# flipperzero-devboard-stlinkv3.net
KiCad netlist of a schematic drawn in Altium Designer
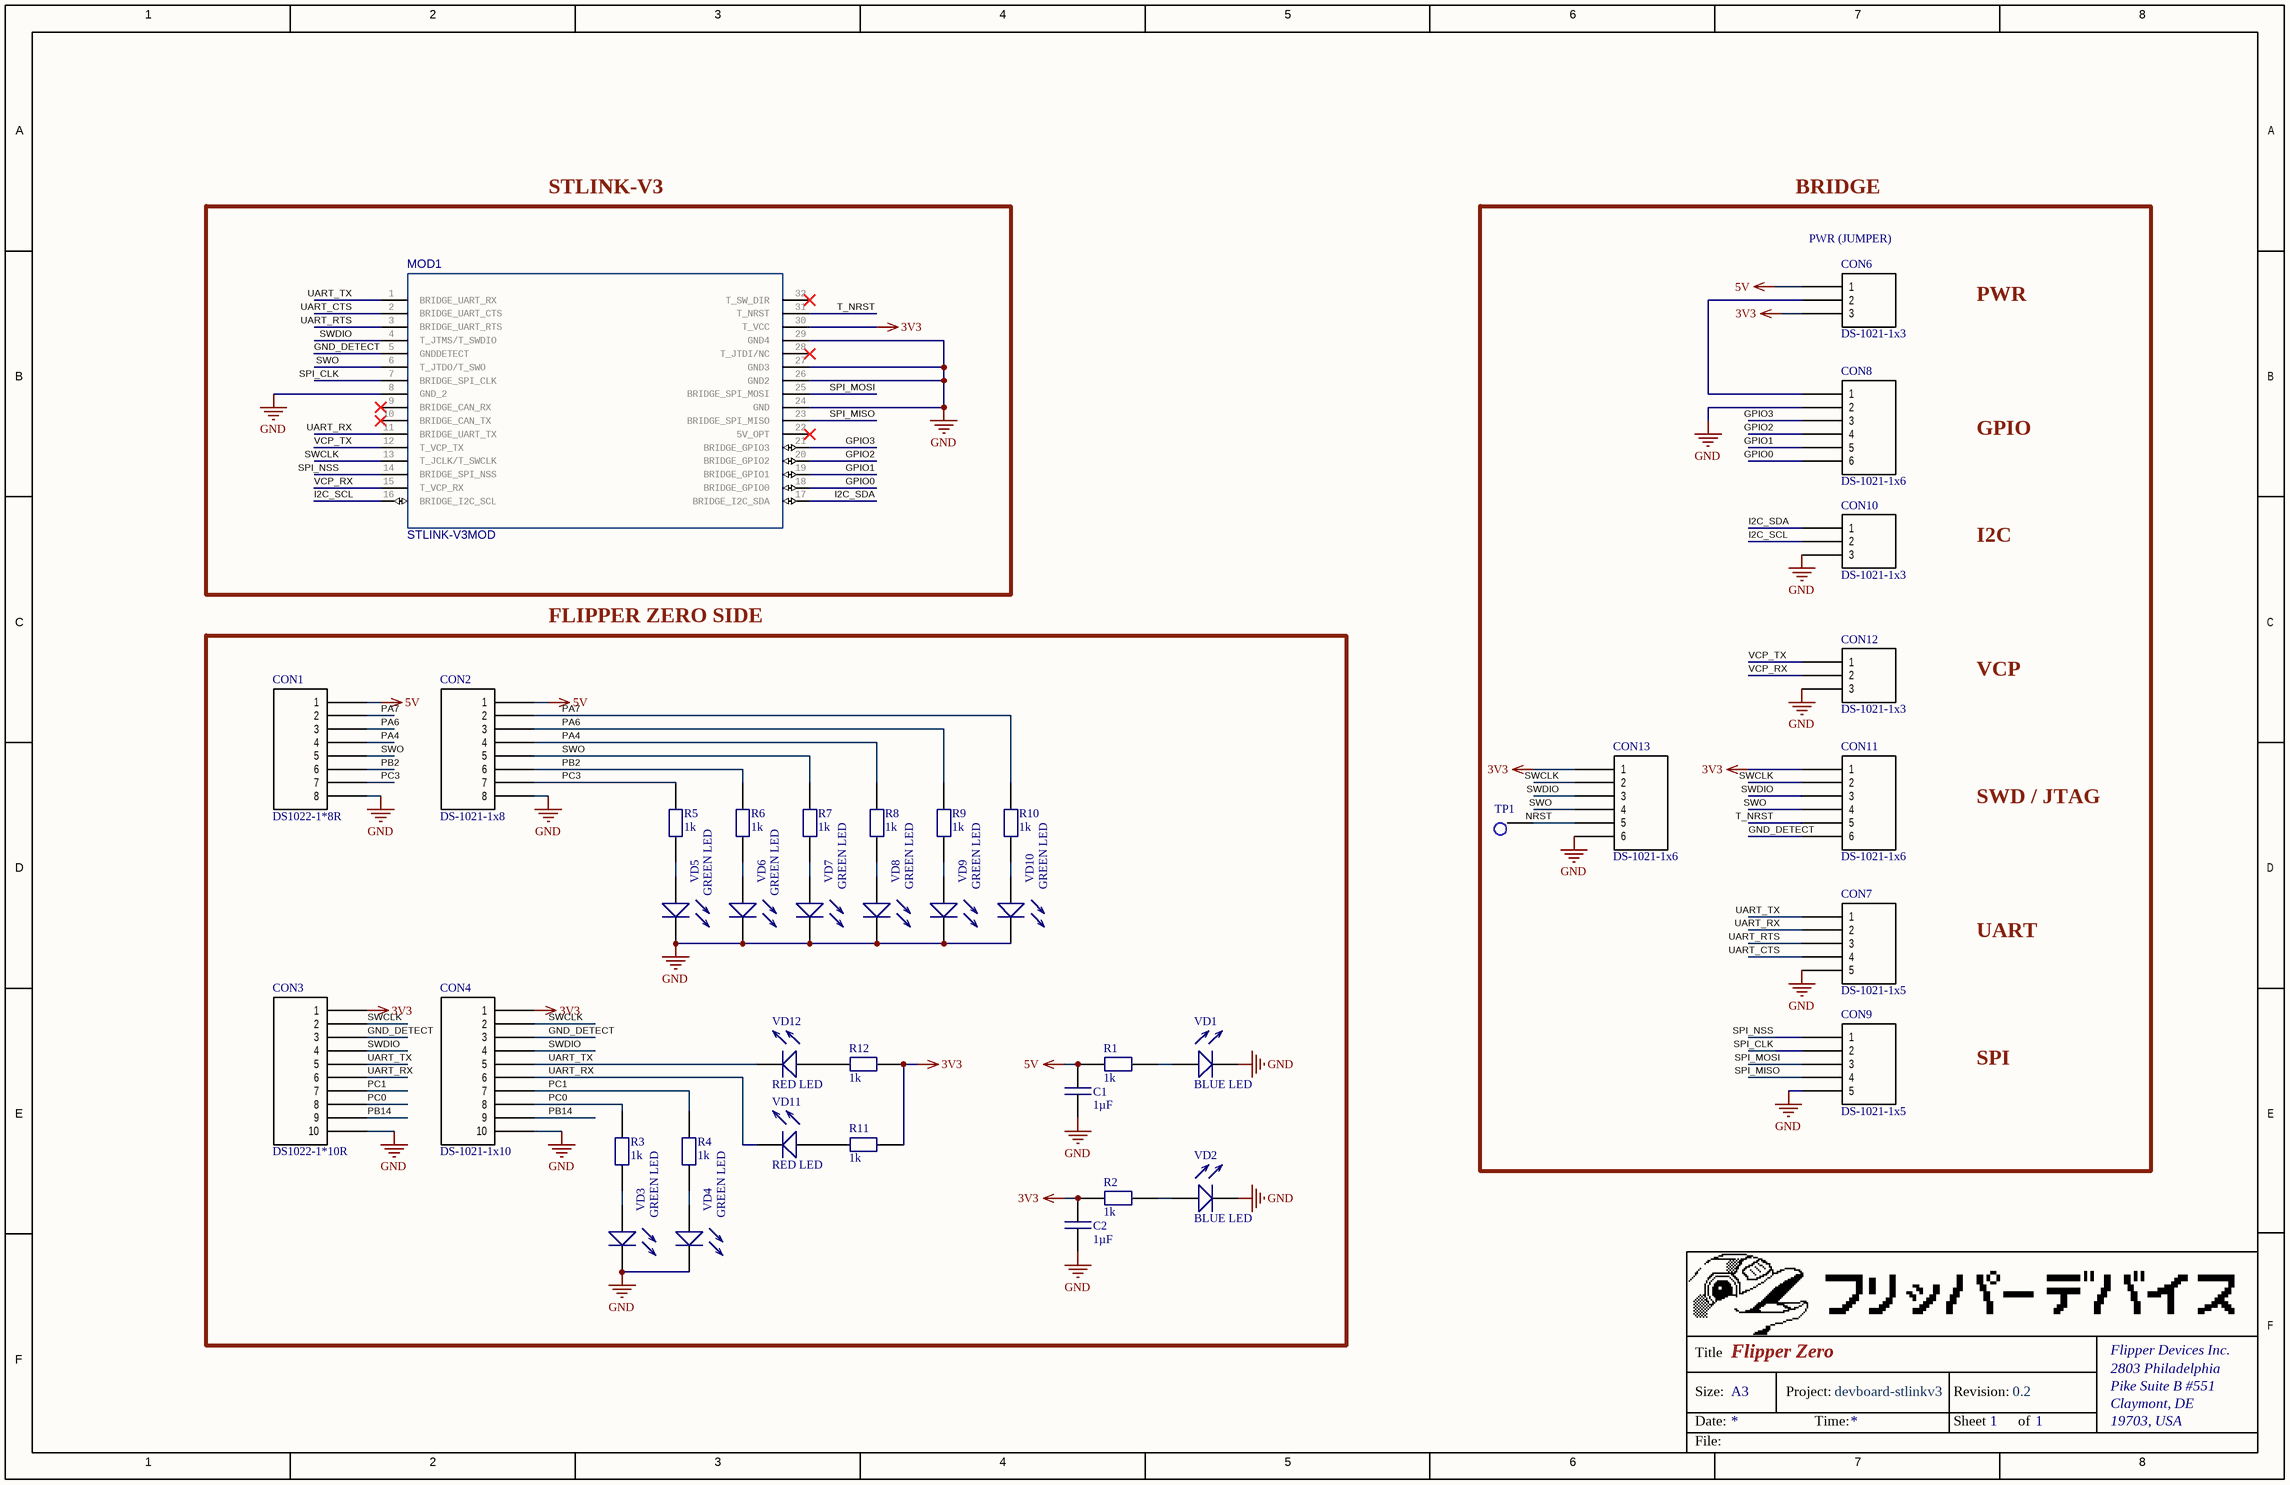
[diagram p0: flipperzero-devboard-stlinkv3.SchDoc]

(export (version "E")
  (design (tool "Eeschema 10.0.6"))
  (components
    (comp (ref "C1")
      (value "1µF")
      (footprint "CAP0603")
      (description "Chip Capacitor")
      (fields (field (name "TOLERANCE") "10%") (field (name "VOLTAGE") "16V"))
      (libsource (lib "") (part "Symbol_1"))
    )
    (comp (ref "C2")
      (value "1µF")
      (footprint "CAP0603")
      (description "Chip Capacitor")
      (fields (field (name "TOLERANCE") "10%") (field (name "VOLTAGE") "16V"))
      (libsource (lib "") (part "Symbol_1"))
    )
    (comp (ref "CON1")
      (value "DS1022-1*8R")
      (footprint "PLS-8R")
      (description "Connector 2.54mm 1х8 Angular Type")
      (fields (field (name "SOURCE") "MIDI.SchLib"))
      (libsource (lib "Flipper Devices") (part "DS-1022-1x8"))
    )
    (comp (ref "CON2")
      (value "DS-1021-1x8")
      (footprint "PLS-8")
      (description "Connector 2.54mm 1х8 Straight Type")
      (fields (field (name "SOURCE") "MIDI.SchLib"))
      (libsource (lib "Flipper Devices") (part "DS-1022-1x8"))
    )
    (comp (ref "CON3")
      (value "DS1022-1*10R")
      (footprint "PLS-10R")
      (description "Connector 2.54mm 1х10 Angular Type")
      (fields (field (name "SOURCE") "MIDI.SchLib"))
      (libsource (lib "Flipper Devices") (part "DS-1022-1x10"))
    )
    (comp (ref "CON4")
      (value "DS-1021-1x10")
      (footprint "PLS-10")
      (description "Connector 2.54mm 1х10 Straight Type")
      (fields (field (name "SOURCE") "MIDI.SchLib"))
      (libsource (lib "Flipper Devices") (part "DS-1021-1x10"))
    )
    (comp (ref "CON6")
      (value "DS-1021-1x3")
      (footprint "PLS-3")
      (description "Connector 2.54mm 1х3 Straight Type")
      (fields (field (name "SOURCE") "MIDI.SchLib"))
      (libsource (lib "Flipper Devices") (part "DS-1021-1x3"))
    )
    (comp (ref "CON7")
      (value "DS-1021-1x5")
      (footprint "PLS-5")
      (description "Connector 2.54mm 1х5 Straight Type")
      (fields (field (name "SOURCE") "MIDI.SchLib"))
      (libsource (lib "Flipper Devices") (part "DS-1021-1x5"))
    )
    (comp (ref "CON8")
      (value "DS-1021-1x6")
      (footprint "PLS-6")
      (description "Connector 2.54mm 1х6 Straight Type")
      (fields (field (name "SOURCE") "MIDI.SchLib"))
      (libsource (lib "Flipper Devices") (part "DS-1021-1x6"))
    )
    (comp (ref "CON9")
      (value "DS-1021-1x5")
      (footprint "PLS-5")
      (description "Connector 2.54mm 1х5 Straight Type")
      (fields (field (name "SOURCE") "MIDI.SchLib"))
      (libsource (lib "Flipper Devices") (part "DS-1021-1x5"))
    )
    (comp (ref "CON10")
      (value "DS-1021-1x3")
      (footprint "PLS-3")
      (description "Connector 2.54mm 1х3 Straight Type")
      (fields (field (name "SOURCE") "MIDI.SchLib"))
      (libsource (lib "Flipper Devices") (part "DS-1021-1x3"))
    )
    (comp (ref "CON11")
      (value "DS-1021-1x6")
      (footprint "PLS-6")
      (description "Connector 2.54mm 1х6 Straight Type")
      (fields (field (name "SOURCE") "MIDI.SchLib"))
      (libsource (lib "Flipper Devices") (part "DS-1021-1x6"))
    )
    (comp (ref "CON12")
      (value "DS-1021-1x3")
      (footprint "PLS-3")
      (description "Connector 2.54mm 1х3 Straight Type")
      (fields (field (name "SOURCE") "MIDI.SchLib"))
      (libsource (lib "Flipper Devices") (part "DS-1021-1x3"))
    )
    (comp (ref "CON13")
      (value "DS-1021-1x6")
      (footprint "PLS-6")
      (description "Connector 2.54mm 1х6 Straight Type")
      (fields (field (name "SOURCE") "MIDI.SchLib"))
      (libsource (lib "Flipper Devices") (part "DS-1021-1x6"))
    )
    (comp (ref "MOD1")
      (value "STLINK-V3MOD")
      (footprint "STLINK-V3MOD")
      (description "STLINK-V3 Compact In-Circuit Debugger and Programmer for STM32 Microcontroller")
      (libsource (lib "Flipper Devices") (part "STLINK-V3MOD"))
    )
    (comp (ref "R1")
      (value "1k")
      (footprint "RESC1608X55X25ML10T15")
      (description "Chip Resistor, 1 KOhm, +/-5%, 0.1 W, -55 to 155 degC, 0603 (1608 Metric)")
      (fields (field (name "POWER") "100mW") (field (name "TOLERANCE") "5%"))
      (libsource (lib "Flipper Devices") (part "Symbol"))
    )
    (comp (ref "R2")
      (value "1k")
      (footprint "RESC1608X55X25ML10T15")
      (description "Chip Resistor, 1 KOhm, +/-5%, 0.1 W, -55 to 155 degC, 0603 (1608 Metric)")
      (fields (field (name "POWER") "100mW") (field (name "TOLERANCE") "5%"))
      (libsource (lib "Flipper Devices") (part "Symbol"))
    )
    (comp (ref "R3")
      (value "1k")
      (footprint "RESC1608X55X25ML10T15")
      (description "Chip Resistor, 1 KOhm, +/-5%, 0.1 W, -55 to 155 degC, 0603 (1608 Metric)")
      (fields (field (name "POWER") "100mW") (field (name "TOLERANCE") "5%"))
      (libsource (lib "Flipper Devices") (part "Symbol"))
    )
    (comp (ref "R4")
      (value "1k")
      (footprint "RESC1608X55X25ML10T15")
      (description "Chip Resistor, 1 KOhm, +/-5%, 0.1 W, -55 to 155 degC, 0603 (1608 Metric)")
      (fields (field (name "POWER") "100mW") (field (name "TOLERANCE") "5%"))
      (libsource (lib "Flipper Devices") (part "Symbol"))
    )
    (comp (ref "R5")
      (value "1k")
      (footprint "RESC1608X55X25ML10T15")
      (description "Chip Resistor, 1 KOhm, +/-5%, 0.1 W, -55 to 155 degC, 0603 (1608 Metric)")
      (fields (field (name "POWER") "100mW") (field (name "TOLERANCE") "5%"))
      (libsource (lib "Flipper Devices") (part "Symbol"))
    )
    (comp (ref "R6")
      (value "1k")
      (footprint "RESC1608X55X25ML10T15")
      (description "Chip Resistor, 1 KOhm, +/-5%, 0.1 W, -55 to 155 degC, 0603 (1608 Metric)")
      (fields (field (name "POWER") "100mW") (field (name "TOLERANCE") "5%"))
      (libsource (lib "Flipper Devices") (part "Symbol"))
    )
    (comp (ref "R7")
      (value "1k")
      (footprint "RESC1608X55X25ML10T15")
      (description "Chip Resistor, 1 KOhm, +/-5%, 0.1 W, -55 to 155 degC, 0603 (1608 Metric)")
      (fields (field (name "POWER") "100mW") (field (name "TOLERANCE") "5%"))
      (libsource (lib "Flipper Devices") (part "Symbol"))
    )
    (comp (ref "R8")
      (value "1k")
      (footprint "RESC1608X55X25ML10T15")
      (description "Chip Resistor, 1 KOhm, +/-5%, 0.1 W, -55 to 155 degC, 0603 (1608 Metric)")
      (fields (field (name "POWER") "100mW") (field (name "TOLERANCE") "5%"))
      (libsource (lib "Flipper Devices") (part "Symbol"))
    )
    (comp (ref "R9")
      (value "1k")
      (footprint "RESC1608X55X25ML10T15")
      (description "Chip Resistor, 1 KOhm, +/-5%, 0.1 W, -55 to 155 degC, 0603 (1608 Metric)")
      (fields (field (name "POWER") "100mW") (field (name "TOLERANCE") "5%"))
      (libsource (lib "Flipper Devices") (part "Symbol"))
    )
    (comp (ref "R10")
      (value "1k")
      (footprint "RESC1608X55X25ML10T15")
      (description "Chip Resistor, 1 KOhm, +/-5%, 0.1 W, -55 to 155 degC, 0603 (1608 Metric)")
      (fields (field (name "POWER") "100mW") (field (name "TOLERANCE") "5%"))
      (libsource (lib "Flipper Devices") (part "Symbol"))
    )
    (comp (ref "R11")
      (value "1k")
      (footprint "RESC1608X55X25ML10T15")
      (description "Chip Resistor, 1 KOhm, +/-5%, 0.1 W, -55 to 155 degC, 0603 (1608 Metric)")
      (fields (field (name "POWER") "100mW") (field (name "TOLERANCE") "5%"))
      (libsource (lib "Flipper Devices") (part "Symbol"))
    )
    (comp (ref "R12")
      (value "1k")
      (footprint "RESC1608X55X25ML10T15")
      (description "Chip Resistor, 1 KOhm, +/-5%, 0.1 W, -55 to 155 degC, 0603 (1608 Metric)")
      (fields (field (name "POWER") "100mW") (field (name "TOLERANCE") "5%"))
      (libsource (lib "Flipper Devices") (part "Symbol"))
    )
    (comp (ref "TP1")
      (value "Control_point")
      (footprint "control point_1mm")
      (description "Testpoint")
      (libsource (lib "Flipper Devices") (part "control point"))
    )
    (comp (ref "VD1")
      (value "BLUE LED")
      (footprint "LED 0603")
      (description "LED")
      (libsource (lib "Flipper Devices") (part "VSMY14940"))
    )
    (comp (ref "VD2")
      (value "BLUE LED")
      (footprint "LED 0603")
      (description "LED")
      (libsource (lib "Flipper Devices") (part "VSMY14940"))
    )
    (comp (ref "VD3")
      (value "GREEN LED")
      (footprint "LED 0603")
      (description "LED")
      (libsource (lib "Flipper Devices") (part "VSMY14940"))
    )
    (comp (ref "VD4")
      (value "GREEN LED")
      (footprint "LED 0603")
      (description "LED")
      (libsource (lib "Flipper Devices") (part "VSMY14940"))
    )
    (comp (ref "VD5")
      (value "GREEN LED")
      (footprint "LED 0603")
      (description "LED")
      (libsource (lib "Flipper Devices") (part "VSMY14940"))
    )
    (comp (ref "VD6")
      (value "GREEN LED")
      (footprint "LED 0603")
      (description "LED")
      (libsource (lib "Flipper Devices") (part "VSMY14940"))
    )
    (comp (ref "VD7")
      (value "GREEN LED")
      (footprint "LED 0603")
      (description "LED")
      (libsource (lib "Flipper Devices") (part "VSMY14940"))
    )
    (comp (ref "VD8")
      (value "GREEN LED")
      (footprint "LED 0603")
      (description "LED")
      (libsource (lib "Flipper Devices") (part "VSMY14940"))
    )
    (comp (ref "VD9")
      (value "GREEN LED")
      (footprint "LED 0603")
      (description "LED")
      (libsource (lib "Flipper Devices") (part "VSMY14940"))
    )
    (comp (ref "VD10")
      (value "GREEN LED")
      (footprint "LED 0603")
      (description "LED")
      (libsource (lib "Flipper Devices") (part "VSMY14940"))
    )
    (comp (ref "VD11")
      (value "RED LED")
      (footprint "LED 0603")
      (description "LED")
      (libsource (lib "Flipper Devices") (part "VSMY14940"))
    )
    (comp (ref "VD12")
      (value "RED LED")
      (footprint "LED 0603")
      (description "LED")
      (libsource (lib "Flipper Devices") (part "VSMY14940"))
    )
  )
  (nets
    (net (code "1") (name "/GND_DETECT") (class "Default")
      (node (ref "CON11") (pin "6") (pinfunction "6_6") (pintype "passive"))
      (node (ref "CON3") (pin "3") (pinfunction "3_3") (pintype "passive"))
      (node (ref "CON4") (pin "3") (pinfunction "3_3") (pintype "passive"))
      (node (ref "MOD1") (pin "5") (pinfunction "GNDDETECT_5") (pintype "passive"))
    )
    (net (code "2") (name "/GPIO0") (class "Default")
      (node (ref "CON8") (pin "6") (pinfunction "6_6") (pintype "passive"))
      (node (ref "MOD1") (pin "18") (pinfunction "BRIDGE_GPIO0_18") (pintype "bidirectional"))
    )
    (net (code "3") (name "/GPIO1") (class "Default")
      (node (ref "CON8") (pin "5") (pinfunction "5_5") (pintype "passive"))
      (node (ref "MOD1") (pin "19") (pinfunction "BRIDGE_GPIO1_19") (pintype "bidirectional"))
    )
    (net (code "4") (name "/GPIO2") (class "Default")
      (node (ref "CON8") (pin "4") (pinfunction "4_4") (pintype "passive"))
      (node (ref "MOD1") (pin "20") (pinfunction "BRIDGE_GPIO2_20") (pintype "bidirectional"))
    )
    (net (code "5") (name "/GPIO3") (class "Default")
      (node (ref "CON8") (pin "3") (pinfunction "3_3") (pintype "passive"))
      (node (ref "MOD1") (pin "21") (pinfunction "BRIDGE_GPIO3_21") (pintype "bidirectional"))
    )
    (net (code "6") (name "/I2C_SCL") (class "Default")
      (node (ref "CON10") (pin "2") (pinfunction "2_2") (pintype "passive"))
      (node (ref "MOD1") (pin "16") (pinfunction "BRIDGE_I2C_SCL_16") (pintype "bidirectional"))
    )
    (net (code "7") (name "/I2C_SDA") (class "Default")
      (node (ref "CON10") (pin "1") (pinfunction "1_1") (pintype "passive"))
      (node (ref "MOD1") (pin "17") (pinfunction "BRIDGE_I2C_SDA_17") (pintype "bidirectional"))
    )
    (net (code "8") (name "/NRST") (class "Default")
      (node (ref "CON13") (pin "5") (pinfunction "5_5") (pintype "passive"))
      (node (ref "TP1") (pin "1") (pinfunction "1_1") (pintype "passive"))
    )
    (net (code "9") (name "/PA4") (class "Default")
      (node (ref "CON1") (pin "4") (pinfunction "4_4") (pintype "passive"))
      (node (ref "CON2") (pin "4") (pinfunction "4_4") (pintype "passive"))
      (node (ref "R8") (pin "1") (pinfunction "1_1") (pintype "passive"))
    )
    (net (code "10") (name "/PA6") (class "Default")
      (node (ref "CON1") (pin "3") (pinfunction "3_3") (pintype "passive"))
      (node (ref "CON2") (pin "3") (pinfunction "3_3") (pintype "passive"))
      (node (ref "R9") (pin "1") (pinfunction "1_1") (pintype "passive"))
    )
    (net (code "11") (name "/PA7") (class "Default")
      (node (ref "CON1") (pin "2") (pinfunction "2_2") (pintype "passive"))
      (node (ref "CON2") (pin "2") (pinfunction "2_2") (pintype "passive"))
      (node (ref "R10") (pin "1") (pinfunction "1_1") (pintype "passive"))
    )
    (net (code "12") (name "/PB2") (class "Default")
      (node (ref "CON1") (pin "6") (pinfunction "6_6") (pintype "passive"))
      (node (ref "CON2") (pin "6") (pinfunction "6_6") (pintype "passive"))
      (node (ref "R6") (pin "1") (pinfunction "1_1") (pintype "passive"))
    )
    (net (code "13") (name "/PB14") (class "Default")
      (node (ref "CON3") (pin "9") (pinfunction "9_9") (pintype "passive"))
      (node (ref "CON4") (pin "9") (pinfunction "9_9") (pintype "passive"))
    )
    (net (code "14") (name "/PC0") (class "Default")
      (node (ref "CON3") (pin "8") (pinfunction "8_8") (pintype "passive"))
      (node (ref "CON4") (pin "8") (pinfunction "8_8") (pintype "passive"))
      (node (ref "R3") (pin "1") (pinfunction "1_1") (pintype "passive"))
    )
    (net (code "15") (name "/PC1") (class "Default")
      (node (ref "CON3") (pin "7") (pinfunction "7_7") (pintype "passive"))
      (node (ref "CON4") (pin "7") (pinfunction "7_7") (pintype "passive"))
      (node (ref "R4") (pin "1") (pinfunction "1_1") (pintype "passive"))
    )
    (net (code "16") (name "/PC3") (class "Default")
      (node (ref "CON1") (pin "7") (pinfunction "7_7") (pintype "passive"))
      (node (ref "CON2") (pin "7") (pinfunction "7_7") (pintype "passive"))
      (node (ref "R5") (pin "1") (pinfunction "1_1") (pintype "passive"))
    )
    (net (code "17") (name "/SPI_CLK") (class "Default")
      (node (ref "CON9") (pin "2") (pinfunction "2_2") (pintype "passive"))
      (node (ref "MOD1") (pin "7") (pinfunction "BRIDGE_SPI_CLK_7") (pintype "passive"))
    )
    (net (code "18") (name "/SPI_MISO") (class "Default")
      (node (ref "CON9") (pin "4") (pinfunction "4_4") (pintype "passive"))
      (node (ref "MOD1") (pin "23") (pinfunction "BRIDGE_SPI_MISO_23") (pintype "passive"))
    )
    (net (code "19") (name "/SPI_MOSI") (class "Default")
      (node (ref "CON9") (pin "3") (pinfunction "3_3") (pintype "passive"))
      (node (ref "MOD1") (pin "25") (pinfunction "BRIDGE_SPI_MOSI_25") (pintype "passive"))
    )
    (net (code "20") (name "/SPI_NSS") (class "Default")
      (node (ref "CON9") (pin "1") (pinfunction "1_1") (pintype "passive"))
      (node (ref "MOD1") (pin "14") (pinfunction "BRIDGE_SPI_NSS_14") (pintype "passive"))
    )
    (net (code "21") (name "/SWCLK") (class "Default")
      (node (ref "CON11") (pin "2") (pinfunction "2_2") (pintype "passive"))
      (node (ref "CON13") (pin "2") (pinfunction "2_2") (pintype "passive"))
      (node (ref "CON3") (pin "2") (pinfunction "2_2") (pintype "passive"))
      (node (ref "CON4") (pin "2") (pinfunction "2_2") (pintype "passive"))
      (node (ref "MOD1") (pin "13") (pinfunction "T_JCLK/T_SWCLK_13") (pintype "passive"))
    )
    (net (code "22") (name "/SWDIO") (class "Default")
      (node (ref "CON11") (pin "3") (pinfunction "3_3") (pintype "passive"))
      (node (ref "CON13") (pin "3") (pinfunction "3_3") (pintype "passive"))
      (node (ref "CON3") (pin "4") (pinfunction "4_4") (pintype "passive"))
      (node (ref "CON4") (pin "4") (pinfunction "4_4") (pintype "passive"))
      (node (ref "MOD1") (pin "4") (pinfunction "T_JTMS/T_SWDIO_4") (pintype "passive"))
    )
    (net (code "23") (name "/SWO") (class "Default")
      (node (ref "CON1") (pin "5") (pinfunction "5_5") (pintype "passive"))
      (node (ref "CON11") (pin "4") (pinfunction "4_4") (pintype "passive"))
      (node (ref "CON13") (pin "4") (pinfunction "4_4") (pintype "passive"))
      (node (ref "CON2") (pin "5") (pinfunction "5_5") (pintype "passive"))
      (node (ref "MOD1") (pin "6") (pinfunction "T_JTDO/T_SWO_6") (pintype "passive"))
      (node (ref "R7") (pin "1") (pinfunction "1_1") (pintype "passive"))
    )
    (net (code "24") (name "/T_NRST") (class "Default")
      (node (ref "CON11") (pin "5") (pinfunction "5_5") (pintype "passive"))
      (node (ref "MOD1") (pin "31") (pinfunction "T_NRST_31") (pintype "passive"))
    )
    (net (code "25") (name "/UART_CTS") (class "Default")
      (node (ref "CON7") (pin "4") (pinfunction "4_4") (pintype "passive"))
      (node (ref "MOD1") (pin "2") (pinfunction "BRIDGE_UART_CTS_2") (pintype "passive"))
    )
    (net (code "26") (name "/UART_RTS") (class "Default")
      (node (ref "CON7") (pin "3") (pinfunction "3_3") (pintype "passive"))
      (node (ref "MOD1") (pin "3") (pinfunction "BRIDGE_UART_RTS_3") (pintype "passive"))
    )
    (net (code "27") (name "/UART_RX") (class "Default")
      (node (ref "CON3") (pin "6") (pinfunction "6_6") (pintype "passive"))
      (node (ref "CON4") (pin "6") (pinfunction "6_6") (pintype "passive"))
      (node (ref "CON7") (pin "2") (pinfunction "2_2") (pintype "passive"))
      (node (ref "MOD1") (pin "11") (pinfunction "BRIDGE_UART_TX_11") (pintype "passive"))
      (node (ref "VD11") (pin "1") (pinfunction "1_1") (pintype "passive"))
    )
    (net (code "28") (name "/UART_TX") (class "Default")
      (node (ref "CON3") (pin "5") (pinfunction "5_5") (pintype "passive"))
      (node (ref "CON4") (pin "5") (pinfunction "5_5") (pintype "passive"))
      (node (ref "CON7") (pin "1") (pinfunction "1_1") (pintype "passive"))
      (node (ref "MOD1") (pin "1") (pinfunction "BRIDGE_UART_RX_1") (pintype "passive"))
      (node (ref "VD12") (pin "1") (pinfunction "1_1") (pintype "passive"))
    )
    (net (code "29") (name "/VCP_RX") (class "Default")
      (node (ref "CON12") (pin "2") (pinfunction "2_2") (pintype "passive"))
      (node (ref "MOD1") (pin "15") (pinfunction "T_VCP_RX_15") (pintype "passive"))
    )
    (net (code "30") (name "/VCP_TX") (class "Default")
      (node (ref "CON12") (pin "1") (pinfunction "1_1") (pintype "passive"))
      (node (ref "MOD1") (pin "12") (pinfunction "T_VCP_TX_12") (pintype "passive"))
    )
    (net (code "31") (name "3V3") (class "Default")
      (node (ref "C2") (pin "2") (pinfunction "2_2") (pintype "passive"))
      (node (ref "CON11") (pin "1") (pinfunction "1_1") (pintype "passive"))
      (node (ref "CON13") (pin "1") (pinfunction "1_1") (pintype "passive"))
      (node (ref "CON3") (pin "1") (pinfunction "1_1") (pintype "passive"))
      (node (ref "CON4") (pin "1") (pinfunction "1_1") (pintype "passive"))
      (node (ref "CON6") (pin "3") (pinfunction "3_3") (pintype "passive"))
      (node (ref "MOD1") (pin "30") (pinfunction "T_VCC_30") (pintype "passive"))
      (node (ref "R11") (pin "2") (pinfunction "2_2") (pintype "passive"))
      (node (ref "R12") (pin "2") (pinfunction "2_2") (pintype "passive"))
      (node (ref "R2") (pin "1") (pinfunction "1_1") (pintype "passive"))
    )
    (net (code "32") (name "5V") (class "Default")
      (node (ref "C1") (pin "2") (pinfunction "2_2") (pintype "passive"))
      (node (ref "CON1") (pin "1") (pinfunction "1_1") (pintype "passive"))
      (node (ref "CON2") (pin "1") (pinfunction "1_1") (pintype "passive"))
      (node (ref "CON6") (pin "1") (pinfunction "1_1") (pintype "passive"))
      (node (ref "R1") (pin "1") (pinfunction "1_1") (pintype "passive"))
    )
    (net (code "33") (name "GND") (class "Default")
      (node (ref "C1") (pin "1") (pinfunction "1_1") (pintype "passive"))
      (node (ref "C2") (pin "1") (pinfunction "1_1") (pintype "passive"))
      (node (ref "CON1") (pin "8") (pinfunction "8_8") (pintype "passive"))
      (node (ref "CON10") (pin "3") (pinfunction "3_3") (pintype "passive"))
      (node (ref "CON12") (pin "3") (pinfunction "3_3") (pintype "passive"))
      (node (ref "CON13") (pin "6") (pinfunction "6_6") (pintype "passive"))
      (node (ref "CON2") (pin "8") (pinfunction "8_8") (pintype "passive"))
      (node (ref "CON3") (pin "10") (pinfunction "10_10") (pintype "passive"))
      (node (ref "CON4") (pin "10") (pinfunction "10_10") (pintype "passive"))
      (node (ref "CON7") (pin "5") (pinfunction "5_5") (pintype "passive"))
      (node (ref "CON8") (pin "2") (pinfunction "2_2") (pintype "passive"))
      (node (ref "CON9") (pin "5") (pinfunction "5_5") (pintype "passive"))
      (node (ref "MOD1") (pin "24") (pinfunction "GND_24") (pintype "passive"))
      (node (ref "MOD1") (pin "26") (pinfunction "GND2_26") (pintype "passive"))
      (node (ref "MOD1") (pin "27") (pinfunction "GND3_27") (pintype "passive"))
      (node (ref "MOD1") (pin "29") (pinfunction "GND4_29") (pintype "passive"))
      (node (ref "MOD1") (pin "8") (pinfunction "GND_2_8") (pintype "passive"))
      (node (ref "VD1") (pin "1") (pinfunction "1_1") (pintype "passive"))
      (node (ref "VD10") (pin "1") (pinfunction "1_1") (pintype "passive"))
      (node (ref "VD2") (pin "1") (pinfunction "1_1") (pintype "passive"))
      (node (ref "VD3") (pin "1") (pinfunction "1_1") (pintype "passive"))
      (node (ref "VD4") (pin "1") (pinfunction "1_1") (pintype "passive"))
      (node (ref "VD5") (pin "1") (pinfunction "1_1") (pintype "passive"))
      (node (ref "VD6") (pin "1") (pinfunction "1_1") (pintype "passive"))
      (node (ref "VD7") (pin "1") (pinfunction "1_1") (pintype "passive"))
      (node (ref "VD8") (pin "1") (pinfunction "1_1") (pintype "passive"))
      (node (ref "VD9") (pin "1") (pinfunction "1_1") (pintype "passive"))
    )
    (net (code "34") (name "Net-(CON6-Pad2)") (class "Default")
      (node (ref "CON6") (pin "2") (pinfunction "2_2") (pintype "passive"))
      (node (ref "CON8") (pin "1") (pinfunction "1_1") (pintype "passive"))
    )
    (net (code "35") (name "Net-(R1-Pad2)") (class "Default")
      (node (ref "R1") (pin "2") (pinfunction "2_2") (pintype "passive"))
      (node (ref "VD1") (pin "2") (pinfunction "2_2") (pintype "passive"))
    )
    (net (code "36") (name "Net-(R2-Pad2)") (class "Default")
      (node (ref "R2") (pin "2") (pinfunction "2_2") (pintype "passive"))
      (node (ref "VD2") (pin "2") (pinfunction "2_2") (pintype "passive"))
    )
    (net (code "37") (name "Net-(R3-Pad2)") (class "Default")
      (node (ref "R3") (pin "2") (pinfunction "2_2") (pintype "passive"))
      (node (ref "VD3") (pin "2") (pinfunction "2_2") (pintype "passive"))
    )
    (net (code "38") (name "Net-(R4-Pad2)") (class "Default")
      (node (ref "R4") (pin "2") (pinfunction "2_2") (pintype "passive"))
      (node (ref "VD4") (pin "2") (pinfunction "2_2") (pintype "passive"))
    )
    (net (code "39") (name "Net-(R5-Pad2)") (class "Default")
      (node (ref "R5") (pin "2") (pinfunction "2_2") (pintype "passive"))
      (node (ref "VD5") (pin "2") (pinfunction "2_2") (pintype "passive"))
    )
    (net (code "40") (name "Net-(R6-Pad2)") (class "Default")
      (node (ref "R6") (pin "2") (pinfunction "2_2") (pintype "passive"))
      (node (ref "VD6") (pin "2") (pinfunction "2_2") (pintype "passive"))
    )
    (net (code "41") (name "Net-(R7-Pad2)") (class "Default")
      (node (ref "R7") (pin "2") (pinfunction "2_2") (pintype "passive"))
      (node (ref "VD7") (pin "2") (pinfunction "2_2") (pintype "passive"))
    )
    (net (code "42") (name "Net-(R8-Pad2)") (class "Default")
      (node (ref "R8") (pin "2") (pinfunction "2_2") (pintype "passive"))
      (node (ref "VD8") (pin "2") (pinfunction "2_2") (pintype "passive"))
    )
    (net (code "43") (name "Net-(R9-Pad2)") (class "Default")
      (node (ref "R9") (pin "2") (pinfunction "2_2") (pintype "passive"))
      (node (ref "VD9") (pin "2") (pinfunction "2_2") (pintype "passive"))
    )
    (net (code "44") (name "Net-(R10-Pad2)") (class "Default")
      (node (ref "R10") (pin "2") (pinfunction "2_2") (pintype "passive"))
      (node (ref "VD10") (pin "2") (pinfunction "2_2") (pintype "passive"))
    )
    (net (code "45") (name "Net-(R11-Pad1)") (class "Default")
      (node (ref "R11") (pin "1") (pinfunction "1_1") (pintype "passive"))
      (node (ref "VD11") (pin "2") (pinfunction "2_2") (pintype "passive"))
    )
    (net (code "46") (name "Net-(R12-Pad1)") (class "Default")
      (node (ref "R12") (pin "1") (pinfunction "1_1") (pintype "passive"))
      (node (ref "VD12") (pin "2") (pinfunction "2_2") (pintype "passive"))
    )
    (net (code "47") (name "unconnected-(MOD1-5V_OPT-Pad22)") (class "Default")
      (node (ref "MOD1") (pin "22") (pinfunction "5V_OPT_22") (pintype "passive+no_connect"))
    )
    (net (code "48") (name "unconnected-(MOD1-BRIDGE_CAN_RX-Pad9)") (class "Default")
      (node (ref "MOD1") (pin "9") (pinfunction "BRIDGE_CAN_RX_9") (pintype "passive+no_connect"))
    )
    (net (code "49") (name "unconnected-(MOD1-BRIDGE_CAN_TX-Pad10)") (class "Default")
      (node (ref "MOD1") (pin "10") (pinfunction "BRIDGE_CAN_TX_10") (pintype "passive+no_connect"))
    )
    (net (code "50") (name "unconnected-(MOD1-T_JTDI{slash}NC-Pad28)") (class "Default")
      (node (ref "MOD1") (pin "28") (pinfunction "T_JTDI/NC_28") (pintype "passive+no_connect"))
    )
    (net (code "51") (name "unconnected-(MOD1-T_SW_DIR-Pad32)") (class "Default")
      (node (ref "MOD1") (pin "32") (pinfunction "T_SW_DIR_32") (pintype "passive+no_connect"))
    )
  )
)
